# Fuse_Tree.net
KiCad netlist of a schematic drawn in EAGLE
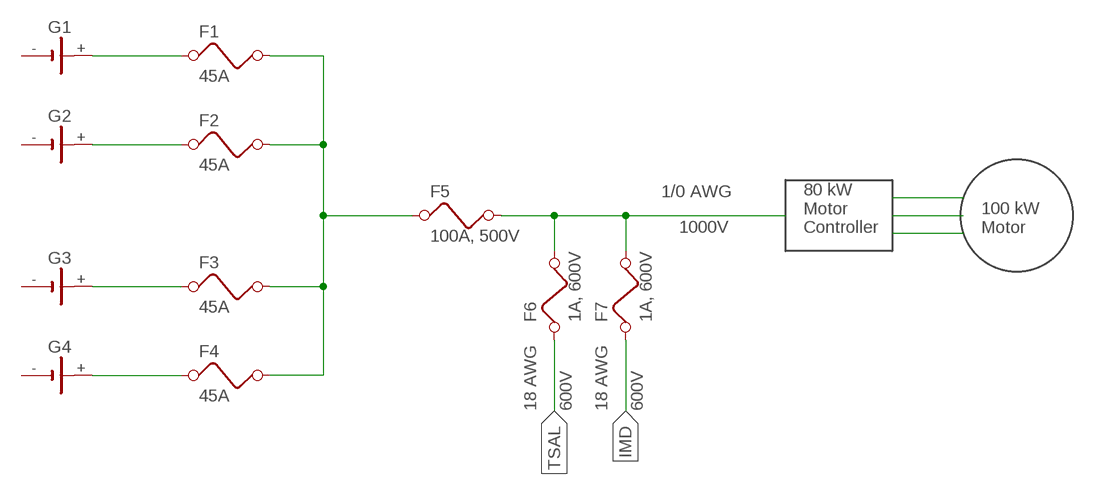
[diagram p0: schematic, sheet 1]

(export (version "E")
  (design (tool "Eeschema 10.0.6"))
  (components
    (comp (ref "F1")
      (value "45A")
      (footprint "eagle-import:FUSE")
      (libsource (lib "eagle-import") (part "FUSE"))
    )
    (comp (ref "F2")
      (value "45A")
      (footprint "eagle-import:FUSE")
      (libsource (lib "eagle-import") (part "FUSE"))
    )
    (comp (ref "F3")
      (value "45A")
      (footprint "eagle-import:FUSE")
      (libsource (lib "eagle-import") (part "FUSE"))
    )
    (comp (ref "F4")
      (value "45A")
      (footprint "eagle-import:FUSE")
      (libsource (lib "eagle-import") (part "FUSE"))
    )
    (comp (ref "F5")
      (value "100A, 500V")
      (footprint "eagle-import:FUSE")
      (libsource (lib "eagle-import") (part "FUSE"))
    )
    (comp (ref "F6")
      (value "1A, 600V")
      (footprint "eagle-import:FUSE")
      (libsource (lib "eagle-import") (part "FUSE"))
    )
    (comp (ref "F7")
      (value "1A, 600V")
      (footprint "eagle-import:FUSE")
      (libsource (lib "eagle-import") (part "FUSE"))
    )
    (comp (ref "G1")
      (value "SL-160AA/PR")
      (footprint "eagle-import:SL-160AA_PR")
      (libsource (lib "eagle-import") (part "SL-160AA/PR"))
    )
    (comp (ref "G2")
      (value "SL-160AA/PR")
      (footprint "eagle-import:SL-160AA_PR")
      (libsource (lib "eagle-import") (part "SL-160AA/PR"))
    )
    (comp (ref "G3")
      (value "SL-160AA/PR")
      (footprint "eagle-import:SL-160AA_PR")
      (libsource (lib "eagle-import") (part "SL-160AA/PR"))
    )
    (comp (ref "G4")
      (value "SL-160AA/PR")
      (footprint "eagle-import:SL-160AA_PR")
      (libsource (lib "eagle-import") (part "SL-160AA/PR"))
    )
  )
  (nets
    (net (code "1") (name "IMD") (class "Default")
      (node (ref "F7") (pin "1") (pinfunction "1_1") (pintype "passive"))
    )
    (net (code "2") (name "Net-(F1-Pad1)") (class "Default")
      (node (ref "F1") (pin "1") (pinfunction "1_1") (pintype "passive"))
      (node (ref "G1") (pin "+") (pinfunction "+_+") (pintype "passive"))
    )
    (net (code "3") (name "Net-(F1-Pad2)") (class "Default")
      (node (ref "F1") (pin "2") (pinfunction "2_2") (pintype "passive"))
      (node (ref "F2") (pin "2") (pinfunction "2_2") (pintype "passive"))
      (node (ref "F3") (pin "2") (pinfunction "2_2") (pintype "passive"))
      (node (ref "F4") (pin "2") (pinfunction "2_2") (pintype "passive"))
      (node (ref "F5") (pin "1") (pinfunction "1_1") (pintype "passive"))
    )
    (net (code "4") (name "Net-(F2-Pad1)") (class "Default")
      (node (ref "F2") (pin "1") (pinfunction "1_1") (pintype "passive"))
      (node (ref "G2") (pin "+") (pinfunction "+_+") (pintype "passive"))
    )
    (net (code "5") (name "Net-(F3-Pad1)") (class "Default")
      (node (ref "F3") (pin "1") (pinfunction "1_1") (pintype "passive"))
      (node (ref "G3") (pin "+") (pinfunction "+_+") (pintype "passive"))
    )
    (net (code "6") (name "Net-(F4-Pad1)") (class "Default")
      (node (ref "F4") (pin "1") (pinfunction "1_1") (pintype "passive"))
      (node (ref "G4") (pin "+") (pinfunction "+_+") (pintype "passive"))
    )
    (net (code "7") (name "Net-(F5-Pad2)") (class "Default")
      (node (ref "F5") (pin "2") (pinfunction "2_2") (pintype "passive"))
      (node (ref "F6") (pin "2") (pinfunction "2_2") (pintype "passive"))
      (node (ref "F7") (pin "2") (pinfunction "2_2") (pintype "passive"))
    )
    (net (code "8") (name "TSAL") (class "Default")
      (node (ref "F6") (pin "1") (pinfunction "1_1") (pintype "passive"))
    )
    (net (code "9") (name "unconnected-(G1-Pad-)") (class "Default")
      (node (ref "G1") (pin "-") (pinfunction "-_-") (pintype "passive"))
    )
    (net (code "10") (name "unconnected-(G2-Pad-)") (class "Default")
      (node (ref "G2") (pin "-") (pinfunction "-_-") (pintype "passive"))
    )
    (net (code "11") (name "unconnected-(G3-Pad-)") (class "Default")
      (node (ref "G3") (pin "-") (pinfunction "-_-") (pintype "passive"))
    )
    (net (code "12") (name "unconnected-(G4-Pad-)") (class "Default")
      (node (ref "G4") (pin "-") (pinfunction "-_-") (pintype "passive"))
    )
  )
)
